# TSL1401CL-Adapter.net
KiCad netlist of a schematic drawn in EAGLE
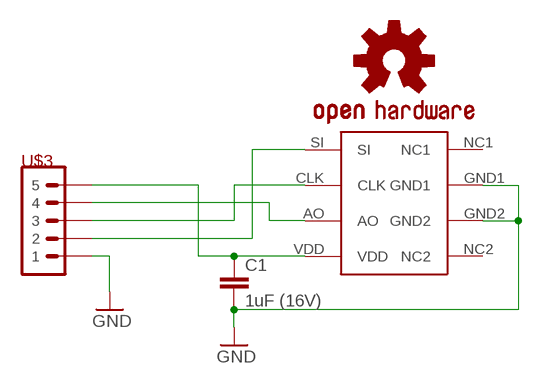
[diagram p0: schematic, sheet 1]

(export (version "E")
  (design (tool "Eeschema 10.0.6"))
  (components
    (comp (ref "C1")
      (value "1uF (16V)")
      (footprint "eagle-import:0603-CAP")
      (libsource (lib "eagle-import") (part "CAP0603-CAP"))
    )
    (comp (ref "U$1")
      (value "TSL1401CL")
      (footprint "eagle-import:TSL1401CL")
      (libsource (lib "eagle-import") (part "TSL1401CL"))
    )
    (comp (ref "U$2")
      (value "OSHW-LOGOM")
      (footprint "eagle-import:OSHW-LOGO-M")
      (libsource (lib "eagle-import") (part "OSHW-LOGOM"))
    )
    (comp (ref "U$3")
      (value "M05")
      (footprint "eagle-import:M05JST-PTH")
      (libsource (lib "eagle-import") (part "M05"))
    )
  )
  (nets
    (net (code "1") (name "GND") (class "Default")
      (node (ref "C1") (pin "2") (pinfunction "2_2") (pintype "passive"))
      (node (ref "U$1") (pin "GND1") (pinfunction "GND1_GND1") (pintype "bidirectional"))
      (node (ref "U$1") (pin "GND2") (pinfunction "GND2_GND2") (pintype "bidirectional"))
      (node (ref "U$3") (pin "P$1") (pinfunction "1_P$1") (pintype "bidirectional"))
    )
    (net (code "2") (name "Net-(U$3-2)") (class "Default")
      (node (ref "U$1") (pin "SI") (pinfunction "SI_SI") (pintype "bidirectional"))
      (node (ref "U$3") (pin "P$2") (pinfunction "2_P$2") (pintype "bidirectional"))
    )
    (net (code "3") (name "Net-(U$3-3)") (class "Default")
      (node (ref "U$1") (pin "CLK") (pinfunction "CLK_CLK") (pintype "bidirectional"))
      (node (ref "U$3") (pin "P$3") (pinfunction "3_P$3") (pintype "bidirectional"))
    )
    (net (code "4") (name "Net-(U$3-4)") (class "Default")
      (node (ref "U$1") (pin "AO") (pinfunction "AO_AO") (pintype "bidirectional"))
      (node (ref "U$3") (pin "P$4") (pinfunction "4_P$4") (pintype "bidirectional"))
    )
    (net (code "5") (name "Net-(U$3-5)") (class "Default")
      (node (ref "C1") (pin "1") (pinfunction "1_1") (pintype "passive"))
      (node (ref "U$1") (pin "VDD") (pinfunction "VDD_VDD") (pintype "bidirectional"))
      (node (ref "U$3") (pin "P$5") (pinfunction "5_P$5") (pintype "bidirectional"))
    )
    (net (code "6") (name "unconnected-(U$1-PadNC1)") (class "Default")
      (node (ref "U$1") (pin "NC1") (pinfunction "NC1_NC1") (pintype "bidirectional"))
    )
    (net (code "7") (name "unconnected-(U$1-PadNC2)") (class "Default")
      (node (ref "U$1") (pin "NC2") (pinfunction "NC2_NC2") (pintype "bidirectional"))
    )
  )
)
